# isa_fdc.net
KiCad netlist of a schematic drawn in Altium Designer
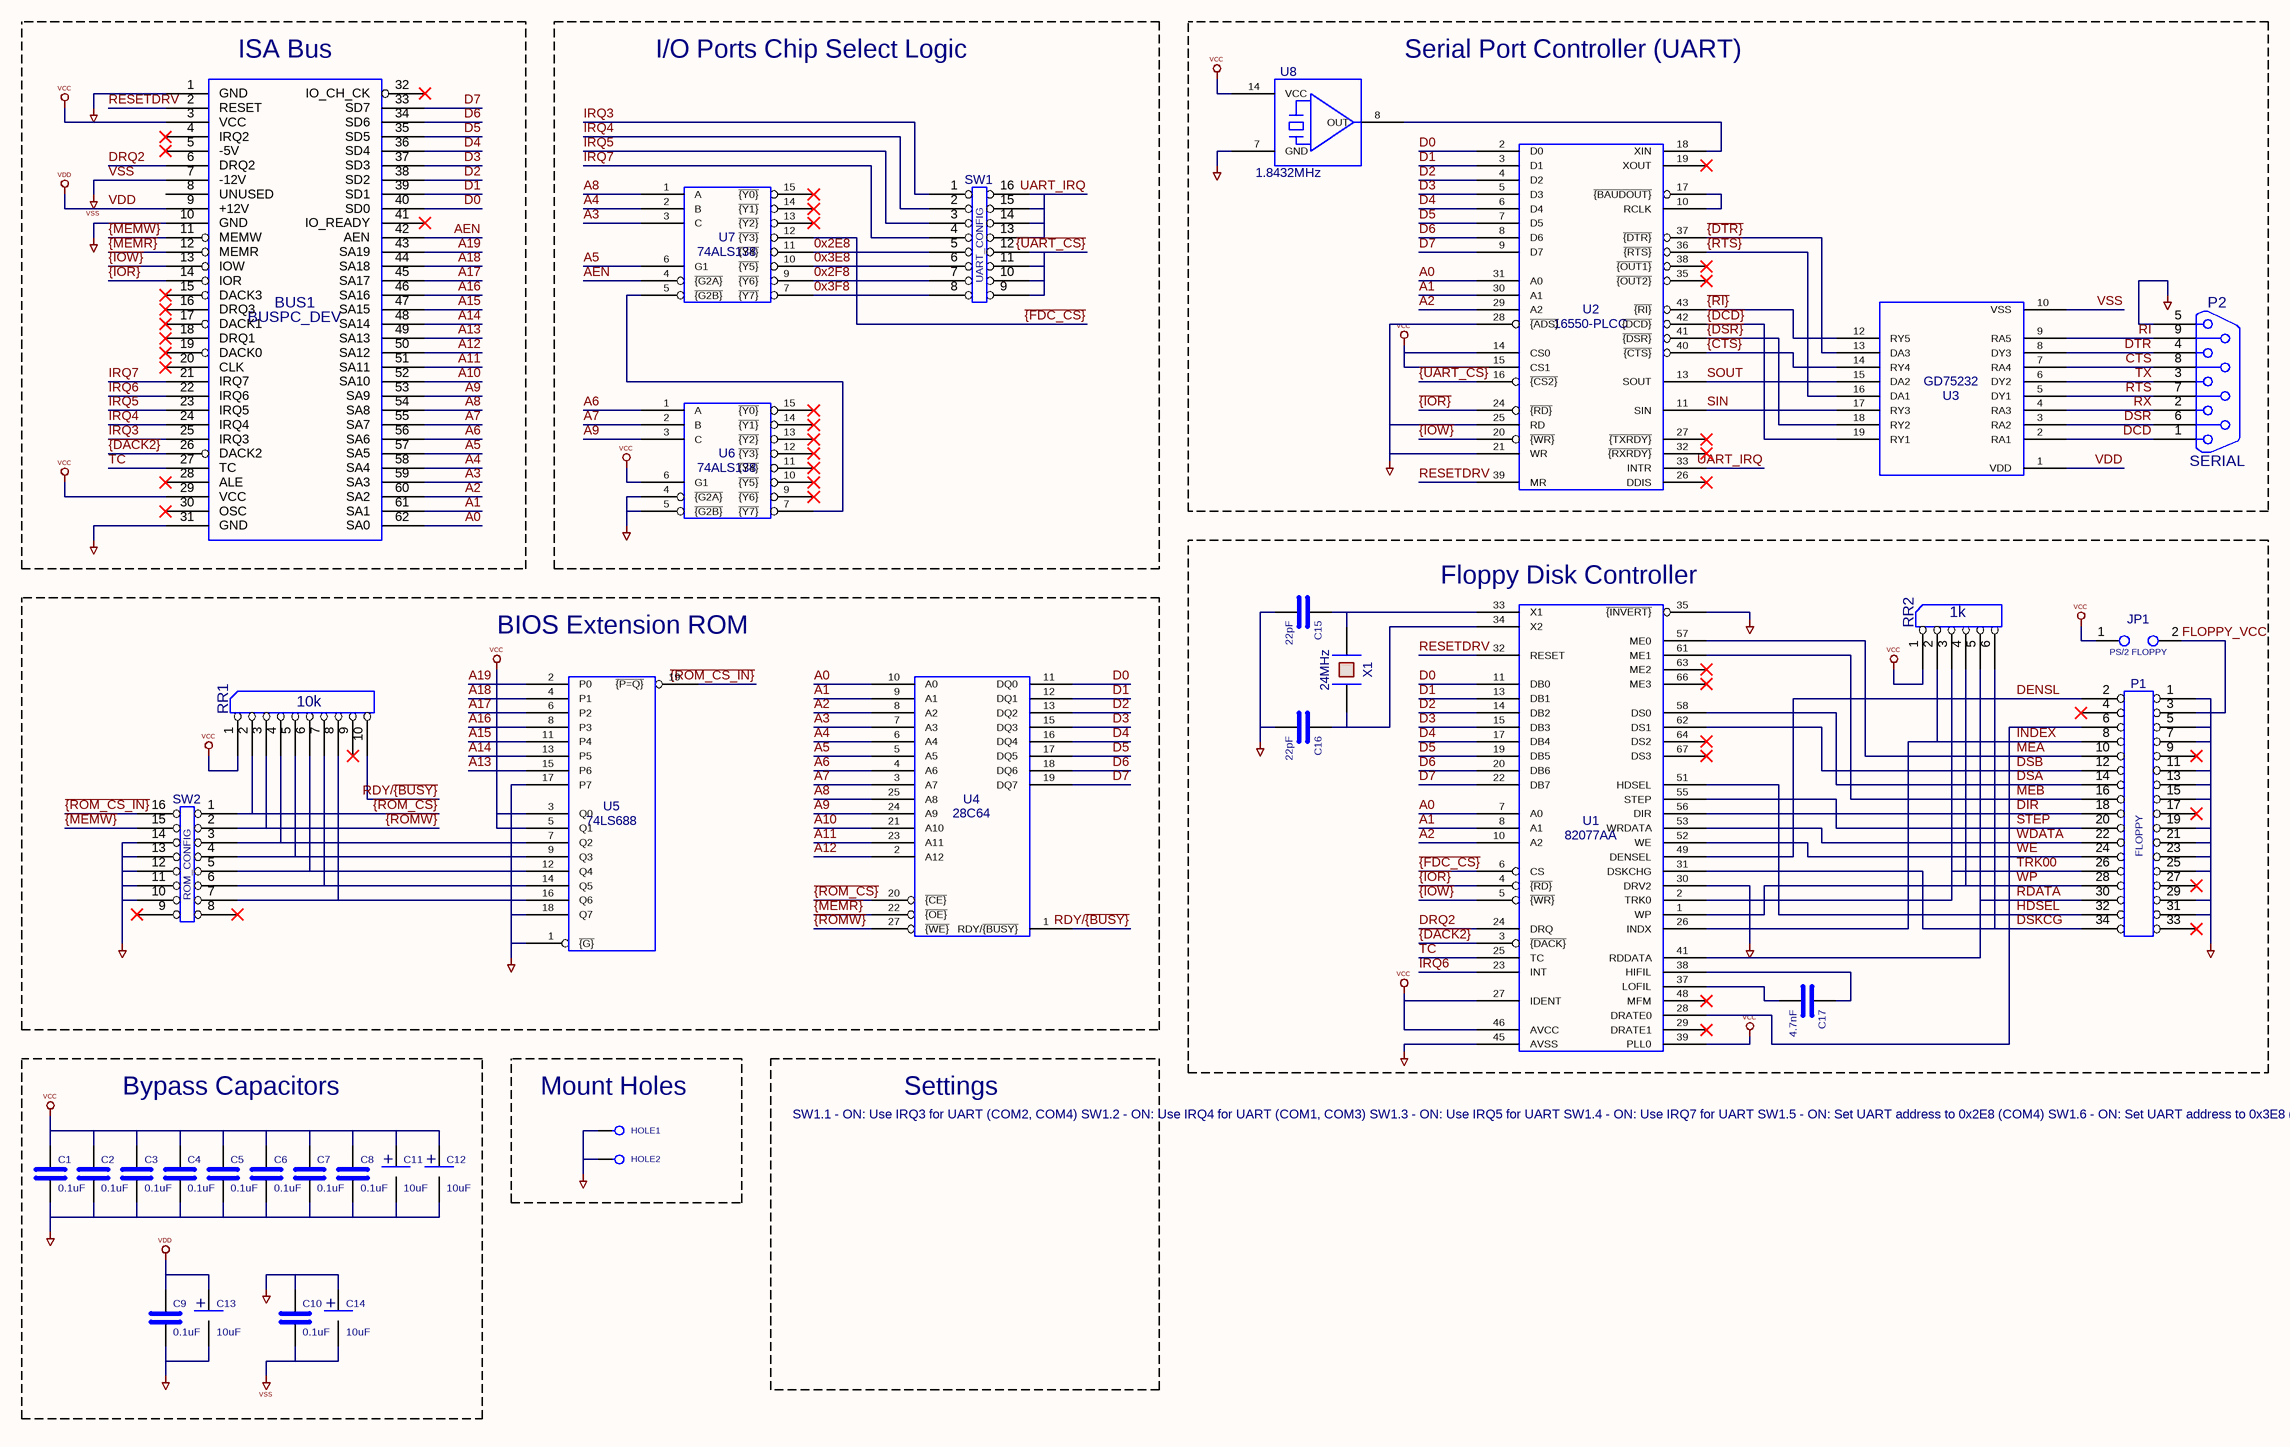
[diagram p0: isa_fdc.SchDoc]

(export (version "E")
  (design (tool "Eeschema 10.0.6"))
  (components
    (comp (ref "BUS1") (value "BUSPC_DEV") (libsource (lib "isa_fdc-rescue") (part "BUSPC_DEV")))
    (comp (ref "C1") (value "0.1uF") (libsource (lib "isa_fdc-rescue") (part "C")))
    (comp (ref "C2") (value "0.1uF") (libsource (lib "isa_fdc-rescue") (part "C")))
    (comp (ref "C3") (value "0.1uF") (libsource (lib "isa_fdc-rescue") (part "C")))
    (comp (ref "C4") (value "0.1uF") (libsource (lib "isa_fdc-rescue") (part "C")))
    (comp (ref "C5") (value "0.1uF") (libsource (lib "isa_fdc-rescue") (part "C")))
    (comp (ref "C6") (value "0.1uF") (libsource (lib "isa_fdc-rescue") (part "C")))
    (comp (ref "C7") (value "0.1uF") (libsource (lib "isa_fdc-rescue") (part "C")))
    (comp (ref "C8") (value "0.1uF") (libsource (lib "isa_fdc-rescue") (part "C")))
    (comp (ref "C9") (value "0.1uF") (libsource (lib "isa_fdc-rescue") (part "C")))
    (comp (ref "C10") (value "0.1uF") (libsource (lib "isa_fdc-rescue") (part "C")))
    (comp (ref "C11") (value "10uF") (libsource (lib "isa_fdc-rescue") (part "CP1")))
    (comp (ref "C12") (value "10uF") (libsource (lib "isa_fdc-rescue") (part "CP1")))
    (comp (ref "C13") (value "10uF") (libsource (lib "isa_fdc-rescue") (part "CP1")))
    (comp (ref "C14") (value "10uF") (libsource (lib "isa_fdc-rescue") (part "CP1")))
    (comp (ref "C15") (value "22pF") (libsource (lib "isa_fdc-rescue") (part "C")))
    (comp (ref "C16") (value "22pF") (libsource (lib "isa_fdc-rescue") (part "C")))
    (comp (ref "C17") (value "4.7nF") (libsource (lib "isa_fdc-rescue") (part "C")))
    (comp (ref "HOLE1") (value "CONN_1") (libsource (lib "isa_fdc-rescue") (part "CONN_1")))
    (comp (ref "HOLE2") (value "CONN_1") (libsource (lib "isa_fdc-rescue") (part "CONN_1")))
    (comp (ref "JP1") (value "PS/2 FLOPPY") (libsource (lib "isa_fdc-rescue") (part "JUMPER")))
    (comp (ref "P1") (value "FLOPPY") (libsource (lib "isa_fdc-rescue") (part "CONN_17X2")))
    (comp (ref "P2") (value "SERIAL") (libsource (lib "isa_fdc-rescue") (part "DB9")))
    (comp (ref "RR1") (value "10k") (libsource (lib "isa_fdc-rescue") (part "RR9")))
    (comp (ref "RR2") (value "1k") (libsource (lib "isa_fdc-rescue") (part "RR5")))
    (comp (ref "SW1") (value "UART_CONFIG") (libsource (lib "") (part "DIL16_1")))
    (comp (ref "SW2") (value "ROM_CONFIG") (libsource (lib "isa_fdc-rescue") (part "DIL16")))
    (comp (ref "U1") (value "82077AA") (libsource (lib "isa_fdc-rescue") (part "82077AA")))
    (comp (ref "U2") (value "16550-PLCC") (libsource (lib "isa_fdc-rescue") (part "16550-PLCC")))
    (comp (ref "U3") (value "GD75232") (libsource (lib "isa_fdc-rescue") (part "GD75232")))
    (comp (ref "U4") (value "28C64") (libsource (lib "isa_fdc-rescue") (part "28C64")))
    (comp (ref "U5") (value "74LS688") (libsource (lib "isa_fdc-rescue") (part "74LS688")))
    (comp (ref "U6") (value "74ALS138") (libsource (lib "isa_fdc-rescue") (part "74LS138")))
    (comp (ref "U7") (value "74ALS138") (libsource (lib "isa_fdc-rescue") (part "74LS138")))
    (comp (ref "U8") (value "1.8432MHz") (libsource (lib "isa_fdc-rescue") (part "OSC")))
    (comp (ref "X1") (value "24MHz") (libsource (lib "isa_fdc-rescue") (part "CRYSTAL")))
  )
  (nets
    (net (code "1") (name "/0x2E8") (class "Default")
      (node (ref "SW1") (pin "5") (pinfunction "5_5") (pintype "passive"))
      (node (ref "U7") (pin "11") (pinfunction "~{{Y4}}_11") (pintype "passive"))
    )
    (net (code "2") (name "/0x2F8") (class "Default")
      (node (ref "SW1") (pin "7") (pinfunction "7_7") (pintype "passive"))
      (node (ref "U7") (pin "9") (pinfunction "~{{Y6}}_9") (pintype "passive"))
    )
    (net (code "3") (name "/0x3E8") (class "Default")
      (node (ref "SW1") (pin "6") (pinfunction "6_6") (pintype "passive"))
      (node (ref "U7") (pin "10") (pinfunction "~{{Y5}}_10") (pintype "passive"))
    )
    (net (code "4") (name "/0x3F8") (class "Default")
      (node (ref "SW1") (pin "8") (pinfunction "8_8") (pintype "passive"))
      (node (ref "U7") (pin "7") (pinfunction "~{{Y7}}_7") (pintype "passive"))
    )
    (net (code "5") (name "/A0") (class "Default")
      (node (ref "BUS1") (pin "62") (pinfunction "SA0_62") (pintype "passive"))
      (node (ref "U1") (pin "7") (pinfunction "A0_7") (pintype "passive"))
      (node (ref "U2") (pin "31") (pinfunction "A0_31") (pintype "passive"))
      (node (ref "U4") (pin "10") (pinfunction "A0_10") (pintype "passive"))
    )
    (net (code "6") (name "/A1") (class "Default")
      (node (ref "BUS1") (pin "61") (pinfunction "SA1_61") (pintype "passive"))
      (node (ref "U1") (pin "8") (pinfunction "A1_8") (pintype "passive"))
      (node (ref "U2") (pin "30") (pinfunction "A1_30") (pintype "passive"))
      (node (ref "U4") (pin "9") (pinfunction "A1_9") (pintype "passive"))
    )
    (net (code "7") (name "/A2") (class "Default")
      (node (ref "BUS1") (pin "60") (pinfunction "SA2_60") (pintype "passive"))
      (node (ref "U1") (pin "10") (pinfunction "A2_10") (pintype "passive"))
      (node (ref "U2") (pin "29") (pinfunction "A2_29") (pintype "passive"))
      (node (ref "U4") (pin "8") (pinfunction "A2_8") (pintype "passive"))
    )
    (net (code "8") (name "/A3") (class "Default")
      (node (ref "BUS1") (pin "59") (pinfunction "SA3_59") (pintype "passive"))
      (node (ref "U4") (pin "7") (pinfunction "A3_7") (pintype "passive"))
      (node (ref "U7") (pin "3") (pinfunction "C_3") (pintype "passive"))
    )
    (net (code "9") (name "/A4") (class "Default")
      (node (ref "BUS1") (pin "58") (pinfunction "SA4_58") (pintype "passive"))
      (node (ref "U4") (pin "6") (pinfunction "A4_6") (pintype "passive"))
      (node (ref "U7") (pin "2") (pinfunction "B_2") (pintype "passive"))
    )
    (net (code "10") (name "/A5") (class "Default")
      (node (ref "BUS1") (pin "57") (pinfunction "SA5_57") (pintype "passive"))
      (node (ref "U4") (pin "5") (pinfunction "A5_5") (pintype "passive"))
      (node (ref "U7") (pin "6") (pinfunction "G1_6") (pintype "passive"))
    )
    (net (code "11") (name "/A6") (class "Default")
      (node (ref "BUS1") (pin "56") (pinfunction "SA6_56") (pintype "passive"))
      (node (ref "U4") (pin "4") (pinfunction "A6_4") (pintype "passive"))
      (node (ref "U6") (pin "1") (pinfunction "A_1") (pintype "passive"))
    )
    (net (code "12") (name "/A7") (class "Default")
      (node (ref "BUS1") (pin "55") (pinfunction "SA7_55") (pintype "passive"))
      (node (ref "U4") (pin "3") (pinfunction "A7_3") (pintype "passive"))
      (node (ref "U6") (pin "2") (pinfunction "B_2") (pintype "passive"))
    )
    (net (code "13") (name "/A8") (class "Default")
      (node (ref "BUS1") (pin "54") (pinfunction "SA8_54") (pintype "passive"))
      (node (ref "U4") (pin "25") (pinfunction "A8_25") (pintype "passive"))
      (node (ref "U7") (pin "1") (pinfunction "A_1") (pintype "passive"))
    )
    (net (code "14") (name "/A9") (class "Default")
      (node (ref "BUS1") (pin "53") (pinfunction "SA9_53") (pintype "passive"))
      (node (ref "U4") (pin "24") (pinfunction "A9_24") (pintype "passive"))
      (node (ref "U6") (pin "3") (pinfunction "C_3") (pintype "passive"))
    )
    (net (code "15") (name "/A10") (class "Default")
      (node (ref "BUS1") (pin "52") (pinfunction "SA10_52") (pintype "passive"))
      (node (ref "U4") (pin "21") (pinfunction "A10_21") (pintype "passive"))
    )
    (net (code "16") (name "/A11") (class "Default")
      (node (ref "BUS1") (pin "51") (pinfunction "SA11_51") (pintype "passive"))
      (node (ref "U4") (pin "23") (pinfunction "A11_23") (pintype "passive"))
    )
    (net (code "17") (name "/A12") (class "Default")
      (node (ref "BUS1") (pin "50") (pinfunction "SA12_50") (pintype "passive"))
      (node (ref "U4") (pin "2") (pinfunction "A12_2") (pintype "passive"))
    )
    (net (code "18") (name "/A13") (class "Default")
      (node (ref "BUS1") (pin "49") (pinfunction "SA13_49") (pintype "passive"))
      (node (ref "U5") (pin "15") (pinfunction "P6_15") (pintype "passive"))
    )
    (net (code "19") (name "/A14") (class "Default")
      (node (ref "BUS1") (pin "48") (pinfunction "SA14_48") (pintype "passive"))
      (node (ref "U5") (pin "13") (pinfunction "P5_13") (pintype "passive"))
    )
    (net (code "20") (name "/A15") (class "Default")
      (node (ref "BUS1") (pin "47") (pinfunction "SA15_47") (pintype "passive"))
      (node (ref "U5") (pin "11") (pinfunction "P4_11") (pintype "passive"))
    )
    (net (code "21") (name "/A16") (class "Default")
      (node (ref "BUS1") (pin "46") (pinfunction "SA16_46") (pintype "passive"))
      (node (ref "U5") (pin "8") (pinfunction "P3_8") (pintype "passive"))
    )
    (net (code "22") (name "/A17") (class "Default")
      (node (ref "BUS1") (pin "45") (pinfunction "SA17_45") (pintype "passive"))
      (node (ref "U5") (pin "6") (pinfunction "P2_6") (pintype "passive"))
    )
    (net (code "23") (name "/A18") (class "Default")
      (node (ref "BUS1") (pin "44") (pinfunction "SA18_44") (pintype "passive"))
      (node (ref "U5") (pin "4") (pinfunction "P1_4") (pintype "passive"))
    )
    (net (code "24") (name "/A19") (class "Default")
      (node (ref "BUS1") (pin "43") (pinfunction "SA19_43") (pintype "passive"))
      (node (ref "U5") (pin "2") (pinfunction "P0_2") (pintype "passive"))
    )
    (net (code "25") (name "/AEN") (class "Default")
      (node (ref "BUS1") (pin "42") (pinfunction "AEN_42") (pintype "passive"))
      (node (ref "U7") (pin "4") (pinfunction "~{{G2A}}_4") (pintype "passive"))
    )
    (net (code "26") (name "/CTS") (class "Default")
      (node (ref "P2") (pin "8") (pinfunction "P8_8") (pintype "passive"))
      (node (ref "U3") (pin "7") (pinfunction "RA4_7") (pintype "passive"))
    )
    (net (code "27") (name "/D0") (class "Default")
      (node (ref "BUS1") (pin "40") (pinfunction "SD0_40") (pintype "passive"))
      (node (ref "U1") (pin "11") (pinfunction "DB0_11") (pintype "passive"))
      (node (ref "U2") (pin "2") (pinfunction "D0_2") (pintype "passive"))
      (node (ref "U4") (pin "11") (pinfunction "DQ0_11") (pintype "passive"))
    )
    (net (code "28") (name "/D1") (class "Default")
      (node (ref "BUS1") (pin "39") (pinfunction "SD1_39") (pintype "passive"))
      (node (ref "U1") (pin "13") (pinfunction "DB1_13") (pintype "passive"))
      (node (ref "U2") (pin "3") (pinfunction "D1_3") (pintype "passive"))
      (node (ref "U4") (pin "12") (pinfunction "DQ1_12") (pintype "passive"))
    )
    (net (code "29") (name "/D2") (class "Default")
      (node (ref "BUS1") (pin "38") (pinfunction "SD2_38") (pintype "passive"))
      (node (ref "U1") (pin "14") (pinfunction "DB2_14") (pintype "passive"))
      (node (ref "U2") (pin "4") (pinfunction "D2_4") (pintype "passive"))
      (node (ref "U4") (pin "13") (pinfunction "DQ2_13") (pintype "passive"))
    )
    (net (code "30") (name "/D3") (class "Default")
      (node (ref "BUS1") (pin "37") (pinfunction "SD3_37") (pintype "passive"))
      (node (ref "U1") (pin "15") (pinfunction "DB3_15") (pintype "passive"))
      (node (ref "U2") (pin "5") (pinfunction "D3_5") (pintype "passive"))
      (node (ref "U4") (pin "15") (pinfunction "DQ3_15") (pintype "passive"))
    )
    (net (code "31") (name "/D4") (class "Default")
      (node (ref "BUS1") (pin "36") (pinfunction "SD4_36") (pintype "passive"))
      (node (ref "U1") (pin "17") (pinfunction "DB4_17") (pintype "passive"))
      (node (ref "U2") (pin "6") (pinfunction "D4_6") (pintype "passive"))
      (node (ref "U4") (pin "16") (pinfunction "DQ4_16") (pintype "passive"))
    )
    (net (code "32") (name "/D5") (class "Default")
      (node (ref "BUS1") (pin "35") (pinfunction "SD5_35") (pintype "passive"))
      (node (ref "U1") (pin "19") (pinfunction "DB5_19") (pintype "passive"))
      (node (ref "U2") (pin "7") (pinfunction "D5_7") (pintype "passive"))
      (node (ref "U4") (pin "17") (pinfunction "DQ5_17") (pintype "passive"))
    )
    (net (code "33") (name "/D6") (class "Default")
      (node (ref "BUS1") (pin "34") (pinfunction "SD6_34") (pintype "passive"))
      (node (ref "U1") (pin "20") (pinfunction "DB6_20") (pintype "passive"))
      (node (ref "U2") (pin "8") (pinfunction "D6_8") (pintype "passive"))
      (node (ref "U4") (pin "18") (pinfunction "DQ6_18") (pintype "passive"))
    )
    (net (code "34") (name "/D7") (class "Default")
      (node (ref "BUS1") (pin "33") (pinfunction "SD7_33") (pintype "passive"))
      (node (ref "U1") (pin "22") (pinfunction "DB7_22") (pintype "passive"))
      (node (ref "U2") (pin "9") (pinfunction "D7_9") (pintype "passive"))
      (node (ref "U4") (pin "19") (pinfunction "DQ7_19") (pintype "passive"))
    )
    (net (code "35") (name "/DCD") (class "Default")
      (node (ref "P2") (pin "1") (pinfunction "1_1") (pintype "passive"))
      (node (ref "U3") (pin "2") (pinfunction "RA1_2") (pintype "passive"))
    )
    (net (code "36") (name "/DENSL") (class "Default")
      (node (ref "P1") (pin "2") (pinfunction "P2_2") (pintype "passive"))
      (node (ref "U1") (pin "49") (pinfunction "DENSEL_49") (pintype "passive"))
    )
    (net (code "37") (name "/DIR") (class "Default")
      (node (ref "P1") (pin "18") (pinfunction "P18_18") (pintype "passive"))
      (node (ref "U1") (pin "56") (pinfunction "DIR_56") (pintype "passive"))
    )
    (net (code "38") (name "/DRQ2") (class "Default")
      (node (ref "BUS1") (pin "6") (pinfunction "DRQ2_6") (pintype "passive"))
      (node (ref "U1") (pin "24") (pinfunction "DRQ_24") (pintype "passive"))
    )
    (net (code "39") (name "/DSA") (class "Default")
      (node (ref "P1") (pin "14") (pinfunction "P14_14") (pintype "passive"))
      (node (ref "U1") (pin "58") (pinfunction "DS0_58") (pintype "passive"))
    )
    (net (code "40") (name "/DSB") (class "Default")
      (node (ref "P1") (pin "12") (pinfunction "P12_12") (pintype "passive"))
      (node (ref "U1") (pin "62") (pinfunction "DS1_62") (pintype "passive"))
    )
    (net (code "41") (name "/DSKCG") (class "Default")
      (node (ref "P1") (pin "34") (pinfunction "P34_34") (pintype "passive"))
      (node (ref "RR2") (pin "6") (pinfunction "6_6") (pintype "passive"))
      (node (ref "U1") (pin "31") (pinfunction "DSKCHG_31") (pintype "passive"))
    )
    (net (code "42") (name "/DSR") (class "Default")
      (node (ref "P2") (pin "6") (pinfunction "P6_6") (pintype "passive"))
      (node (ref "U3") (pin "3") (pinfunction "RA2_3") (pintype "passive"))
    )
    (net (code "43") (name "/DTR") (class "Default")
      (node (ref "P2") (pin "4") (pinfunction "4_4") (pintype "passive"))
      (node (ref "U3") (pin "8") (pinfunction "DY3_8") (pintype "passive"))
    )
    (net (code "44") (name "/FLOPPY_VCC") (class "Default")
      (node (ref "JP1") (pin "2") (pinfunction "2_2") (pintype "passive"))
      (node (ref "P1") (pin "3") (pinfunction "P3_3") (pintype "passive"))
    )
    (net (code "45") (name "/HDSEL") (class "Default")
      (node (ref "P1") (pin "32") (pinfunction "P32_32") (pintype "passive"))
      (node (ref "U1") (pin "51") (pinfunction "HDSEL_51") (pintype "passive"))
    )
    (net (code "46") (name "/INDEX") (class "Default")
      (node (ref "P1") (pin "8") (pinfunction "P8_8") (pintype "passive"))
      (node (ref "RR2") (pin "2") (pinfunction "2_2") (pintype "passive"))
      (node (ref "U1") (pin "26") (pinfunction "INDX_26") (pintype "passive"))
    )
    (net (code "47") (name "/IRQ3") (class "Default")
      (node (ref "BUS1") (pin "25") (pinfunction "IRQ3_25") (pintype "passive"))
      (node (ref "SW1") (pin "1") (pinfunction "1_1") (pintype "passive"))
    )
    (net (code "48") (name "/IRQ4") (class "Default")
      (node (ref "BUS1") (pin "24") (pinfunction "IRQ4_24") (pintype "passive"))
      (node (ref "SW1") (pin "2") (pinfunction "2_2") (pintype "passive"))
    )
    (net (code "49") (name "/IRQ5") (class "Default")
      (node (ref "BUS1") (pin "23") (pinfunction "IRQ5_23") (pintype "passive"))
      (node (ref "SW1") (pin "3") (pinfunction "3_3") (pintype "passive"))
    )
    (net (code "50") (name "/IRQ6") (class "Default")
      (node (ref "BUS1") (pin "22") (pinfunction "IRQ6_22") (pintype "passive"))
      (node (ref "U1") (pin "23") (pinfunction "INT_23") (pintype "passive"))
    )
    (net (code "51") (name "/IRQ7") (class "Default")
      (node (ref "BUS1") (pin "21") (pinfunction "IRQ7_21") (pintype "passive"))
      (node (ref "SW1") (pin "4") (pinfunction "4_4") (pintype "passive"))
    )
    (net (code "52") (name "/MEA") (class "Default")
      (node (ref "P1") (pin "10") (pinfunction "P10_10") (pintype "passive"))
      (node (ref "U1") (pin "57") (pinfunction "ME0_57") (pintype "passive"))
    )
    (net (code "53") (name "/MEB") (class "Default")
      (node (ref "P1") (pin "16") (pinfunction "P16_16") (pintype "passive"))
      (node (ref "U1") (pin "61") (pinfunction "ME1_61") (pintype "passive"))
    )
    (net (code "54") (name "/RDATA") (class "Default")
      (node (ref "P1") (pin "30") (pinfunction "P30_30") (pintype "passive"))
      (node (ref "RR2") (pin "5") (pinfunction "5_5") (pintype "passive"))
      (node (ref "U1") (pin "41") (pinfunction "RDDATA_41") (pintype "passive"))
    )
    (net (code "55") (name "/RDY{slash}~{{BUSY}}") (class "Default")
      (node (ref "RR1") (pin "10") (pinfunction "10_10") (pintype "passive"))
      (node (ref "U4") (pin "1") (pinfunction "RDY/~{{BUSY}}_1") (pintype "passive"))
    )
    (net (code "56") (name "/RESETDRV") (class "Default")
      (node (ref "BUS1") (pin "2") (pinfunction "RESET_2") (pintype "passive"))
      (node (ref "U1") (pin "32") (pinfunction "RESET_32") (pintype "passive"))
      (node (ref "U2") (pin "39") (pinfunction "MR_39") (pintype "passive"))
    )
    (net (code "57") (name "/RI") (class "Default")
      (node (ref "P2") (pin "9") (pinfunction "P9_9") (pintype "passive"))
      (node (ref "U3") (pin "9") (pinfunction "RA5_9") (pintype "passive"))
    )
    (net (code "58") (name "/RTS") (class "Default")
      (node (ref "P2") (pin "7") (pinfunction "P7_7") (pintype "passive"))
      (node (ref "U3") (pin "5") (pinfunction "DY1_5") (pintype "passive"))
    )
    (net (code "59") (name "/RX") (class "Default")
      (node (ref "P2") (pin "2") (pinfunction "2_2") (pintype "passive"))
      (node (ref "U3") (pin "4") (pinfunction "RA3_4") (pintype "passive"))
    )
    (net (code "60") (name "/SIN") (class "Default")
      (node (ref "U2") (pin "11") (pinfunction "SIN_11") (pintype "passive"))
      (node (ref "U3") (pin "17") (pinfunction "RY3_17") (pintype "passive"))
    )
    (net (code "61") (name "/SOUT") (class "Default")
      (node (ref "U2") (pin "13") (pinfunction "SOUT_13") (pintype "passive"))
      (node (ref "U3") (pin "15") (pinfunction "DA2_15") (pintype "passive"))
    )
    (net (code "62") (name "/STEP") (class "Default")
      (node (ref "P1") (pin "20") (pinfunction "P20_20") (pintype "passive"))
      (node (ref "U1") (pin "55") (pinfunction "STEP_55") (pintype "passive"))
    )
    (net (code "63") (name "/TC") (class "Default")
      (node (ref "BUS1") (pin "27") (pinfunction "TC_27") (pintype "passive"))
      (node (ref "U1") (pin "25") (pinfunction "TC_25") (pintype "passive"))
    )
    (net (code "64") (name "/TRK00") (class "Default")
      (node (ref "P1") (pin "26") (pinfunction "P26_26") (pintype "passive"))
      (node (ref "RR2") (pin "3") (pinfunction "3_3") (pintype "passive"))
      (node (ref "U1") (pin "2") (pinfunction "TRK0_2") (pintype "passive"))
    )
    (net (code "65") (name "/TX") (class "Default")
      (node (ref "P2") (pin "3") (pinfunction "3_3") (pintype "passive"))
      (node (ref "U3") (pin "6") (pinfunction "DY2_6") (pintype "passive"))
    )
    (net (code "66") (name "/UART_IRQ") (class "Default")
      (node (ref "SW1") (pin "13") (pinfunction "13_13") (pintype "passive"))
      (node (ref "SW1") (pin "14") (pinfunction "14_14") (pintype "passive"))
      (node (ref "SW1") (pin "15") (pinfunction "15_15") (pintype "passive"))
      (node (ref "SW1") (pin "16") (pinfunction "16_16") (pintype "passive"))
      (node (ref "U2") (pin "33") (pinfunction "INTR_33") (pintype "passive"))
    )
    (net (code "67") (name "/WDATA") (class "Default")
      (node (ref "P1") (pin "22") (pinfunction "P22_22") (pintype "passive"))
      (node (ref "U1") (pin "53") (pinfunction "WRDATA_53") (pintype "passive"))
    )
    (net (code "68") (name "/WE") (class "Default")
      (node (ref "P1") (pin "24") (pinfunction "P24_24") (pintype "passive"))
      (node (ref "U1") (pin "52") (pinfunction "WE_52") (pintype "passive"))
    )
    (net (code "69") (name "/WP") (class "Default")
      (node (ref "P1") (pin "28") (pinfunction "P28_28") (pintype "passive"))
      (node (ref "RR2") (pin "4") (pinfunction "4_4") (pintype "passive"))
      (node (ref "U1") (pin "1") (pinfunction "WP_1") (pintype "passive"))
    )
    (net (code "70") (name "/~{{CTS}}") (class "Default")
      (node (ref "U2") (pin "40") (pinfunction "~{{CTS}}_40") (pintype "passive"))
      (node (ref "U3") (pin "14") (pinfunction "RY4_14") (pintype "passive"))
    )
    (net (code "71") (name "/~{{DACK2}}") (class "Default")
      (node (ref "BUS1") (pin "26") (pinfunction "DACK2_26") (pintype "passive"))
      (node (ref "U1") (pin "3") (pinfunction "~{{DACK}}_3") (pintype "passive"))
    )
    (net (code "72") (name "/~{{DCD}}") (class "Default")
      (node (ref "U2") (pin "42") (pinfunction "~{{DCD}}_42") (pintype "passive"))
      (node (ref "U3") (pin "19") (pinfunction "RY1_19") (pintype "passive"))
    )
    (net (code "73") (name "/~{{DSR}}") (class "Default")
      (node (ref "U2") (pin "41") (pinfunction "~{{DSR}}_41") (pintype "passive"))
      (node (ref "U3") (pin "18") (pinfunction "RY2_18") (pintype "passive"))
    )
    (net (code "74") (name "/~{{DTR}}") (class "Default")
      (node (ref "U2") (pin "37") (pinfunction "~{{DTR}}_37") (pintype "passive"))
      (node (ref "U3") (pin "13") (pinfunction "DA3_13") (pintype "passive"))
    )
    (net (code "75") (name "/~{{FDC_CS}}") (class "Default")
      (node (ref "U1") (pin "6") (pinfunction "CS_6") (pintype "passive"))
      (node (ref "U7") (pin "12") (pinfunction "~{{Y3}}_12") (pintype "passive"))
    )
    (net (code "76") (name "/~{{IOR}}") (class "Default")
      (node (ref "BUS1") (pin "14") (pinfunction "IOR_14") (pintype "passive"))
      (node (ref "U1") (pin "4") (pinfunction "~{{RD}}_4") (pintype "passive"))
      (node (ref "U2") (pin "24") (pinfunction "~{{RD}}_24") (pintype "passive"))
    )
    (net (code "77") (name "/~{{IOW}}") (class "Default")
      (node (ref "BUS1") (pin "13") (pinfunction "IOW_13") (pintype "passive"))
      (node (ref "U1") (pin "5") (pinfunction "~{{WR}}_5") (pintype "passive"))
      (node (ref "U2") (pin "20") (pinfunction "~{{WR}}_20") (pintype "passive"))
    )
    (net (code "78") (name "/~{{MEMR}}") (class "Default")
      (node (ref "BUS1") (pin "12") (pinfunction "MEMR_12") (pintype "passive"))
      (node (ref "U4") (pin "22") (pinfunction "~{{OE}}_22") (pintype "passive"))
    )
    (net (code "79") (name "/~{{MEMW}}") (class "Default")
      (node (ref "BUS1") (pin "11") (pinfunction "MEMW_11") (pintype "passive"))
      (node (ref "SW2") (pin "15") (pinfunction "15_15") (pintype "passive"))
    )
    (net (code "80") (name "/~{{RI}}") (class "Default")
      (node (ref "U2") (pin "43") (pinfunction "~{{RI}}_43") (pintype "passive"))
      (node (ref "U3") (pin "12") (pinfunction "RY5_12") (pintype "passive"))
    )
    (net (code "81") (name "/~{{ROMW}}") (class "Default")
      (node (ref "RR1") (pin "3") (pinfunction "3_3") (pintype "passive"))
      (node (ref "SW2") (pin "2") (pinfunction "2_2") (pintype "passive"))
      (node (ref "U4") (pin "27") (pinfunction "~{{WE}}_27") (pintype "passive"))
    )
    (net (code "82") (name "/~{{ROM_CS_IN}}") (class "Default")
      (node (ref "SW2") (pin "16") (pinfunction "16_16") (pintype "passive"))
      (node (ref "U5") (pin "19") (pinfunction "~{{P=Q}}_19") (pintype "passive"))
    )
    (net (code "83") (name "/~{{ROM_CS}}") (class "Default")
      (node (ref "RR1") (pin "2") (pinfunction "2_2") (pintype "passive"))
      (node (ref "SW2") (pin "1") (pinfunction "1_1") (pintype "passive"))
      (node (ref "U4") (pin "20") (pinfunction "~{{CE}}_20") (pintype "passive"))
    )
    (net (code "84") (name "/~{{RTS}}") (class "Default")
      (node (ref "U2") (pin "36") (pinfunction "~{{RTS}}_36") (pintype "passive"))
      (node (ref "U3") (pin "16") (pinfunction "DA1_16") (pintype "passive"))
    )
    (net (code "85") (name "/~{{UART_CS}}") (class "Default")
      (node (ref "SW1") (pin "10") (pinfunction "10_10") (pintype "passive"))
      (node (ref "SW1") (pin "11") (pinfunction "11_11") (pintype "passive"))
      (node (ref "SW1") (pin "12") (pinfunction "12_12") (pintype "passive"))
      (node (ref "SW1") (pin "9") (pinfunction "9_9") (pintype "passive"))
      (node (ref "U2") (pin "16") (pinfunction "~{{CS2}}_16") (pintype "passive"))
    )
    (net (code "86") (name "GND") (class "Default")
      (node (ref "BUS1") (pin "1") (pinfunction "GND_1") (pintype "passive"))
      (node (ref "BUS1") (pin "10") (pinfunction "GND_10") (pintype "passive"))
      (node (ref "BUS1") (pin "31") (pinfunction "GND_31") (pintype "passive"))
      (node (ref "C1") (pin "2") (pinfunction "2_2") (pintype "passive"))
      (node (ref "C10") (pin "1") (pinfunction "1_1") (pintype "passive"))
      (node (ref "C11") (pin "2") (pinfunction "2_2") (pintype "passive"))
      (node (ref "C12") (pin "2") (pinfunction "2_2") (pintype "passive"))
      (node (ref "C13") (pin "2") (pinfunction "2_2") (pintype "passive"))
      (node (ref "C14") (pin "1") (pinfunction "1_1") (pintype "passive"))
      (node (ref "C15") (pin "2") (pinfunction "2_2") (pintype "passive"))
      (node (ref "C16") (pin "2") (pinfunction "2_2") (pintype "passive"))
      (node (ref "C2") (pin "2") (pinfunction "2_2") (pintype "passive"))
      (node (ref "C3") (pin "2") (pinfunction "2_2") (pintype "passive"))
      (node (ref "C4") (pin "2") (pinfunction "2_2") (pintype "passive"))
      (node (ref "C5") (pin "2") (pinfunction "2_2") (pintype "passive"))
      (node (ref "C6") (pin "2") (pinfunction "2_2") (pintype "passive"))
      (node (ref "C7") (pin "2") (pinfunction "2_2") (pintype "passive"))
      (node (ref "C8") (pin "2") (pinfunction "2_2") (pintype "passive"))
      (node (ref "C9") (pin "2") (pinfunction "2_2") (pintype "passive"))
      (node (ref "HOLE1") (pin "1") (pinfunction "1_1") (pintype "passive"))
      (node (ref "HOLE2") (pin "1") (pinfunction "1_1") (pintype "passive"))
      (node (ref "P1") (pin "1") (pinfunction "P1_1") (pintype "passive"))
      (node (ref "P1") (pin "11") (pinfunction "P11_11") (pintype "passive"))
      (node (ref "P1") (pin "13") (pinfunction "P13_13") (pintype "passive"))
      (node (ref "P1") (pin "15") (pinfunction "P15_15") (pintype "passive"))
      (node (ref "P1") (pin "19") (pinfunction "P19_19") (pintype "passive"))
      (node (ref "P1") (pin "21") (pinfunction "P21_21") (pintype "passive"))
      (node (ref "P1") (pin "23") (pinfunction "P23_23") (pintype "passive"))
      (node (ref "P1") (pin "25") (pinfunction "25_25") (pintype "passive"))
      (node (ref "P1") (pin "29") (pinfunction "P29_29") (pintype "passive"))
      (node (ref "P1") (pin "31") (pinfunction "P31_31") (pintype "passive"))
      (node (ref "P1") (pin "5") (pinfunction "P5_5") (pintype "passive"))
      (node (ref "P1") (pin "7") (pinfunction "P7_7") (pintype "passive"))
      (node (ref "P2") (pin "5") (pinfunction "5_5") (pintype "passive"))
      (node (ref "SW2") (pin "10") (pinfunction "10_10") (pintype "passive"))
      (node (ref "SW2") (pin "11") (pinfunction "11_11") (pintype "passive"))
      (node (ref "SW2") (pin "12") (pinfunction "12_12") (pintype "passive"))
      (node (ref "SW2") (pin "13") (pinfunction "13_13") (pintype "passive"))
      (node (ref "SW2") (pin "14") (pinfunction "14_14") (pintype "passive"))
      (node (ref "U1") (pin "30") (pinfunction "DRV2_30") (pintype "passive"))
      (node (ref "U1") (pin "35") (pinfunction "~{{INVERT}}_35") (pintype "passive"))
      (node (ref "U1") (pin "45") (pinfunction "AVSS_45") (pintype "passive"))
      (node (ref "U2") (pin "21") (pinfunction "WR_21") (pintype "passive"))
      (node (ref "U2") (pin "25") (pinfunction "RD_25") (pintype "passive"))
      (node (ref "U2") (pin "28") (pinfunction "~{{ADS}}_28") (pintype "passive"))
      (node (ref "U5") (pin "1") (pinfunction "~{{G}}_1") (pintype "passive"))
      (node (ref "U5") (pin "17") (pinfunction "P7_17") (pintype "passive"))
      (node (ref "U5") (pin "18") (pinfunction "Q7_18") (pintype "passive"))
      (node (ref "U6") (pin "4") (pinfunction "~{{G2A}}_4") (pintype "passive"))
      (node (ref "U6") (pin "5") (pinfunction "~{{G2B}}_5") (pintype "passive"))
      (node (ref "U8") (pin "7") (pinfunction "GND_7") (pintype "passive"))
    )
    (net (code "87") (name "Net-(P1-P6)") (class "Default")
      (node (ref "P1") (pin "6") (pinfunction "P6_6") (pintype "passive"))
      (node (ref "U1") (pin "28") (pinfunction "DRATE0_28") (pintype "passive"))
    )
    (net (code "88") (name "Net-(U1-HIFIL)") (class "Default")
      (node (ref "C17") (pin "1") (pinfunction "1_1") (pintype "passive"))
      (node (ref "U1") (pin "38") (pinfunction "HIFIL_38") (pintype "passive"))
    )
    (net (code "89") (name "Net-(U1-LOFIL)") (class "Default")
      (node (ref "C17") (pin "2") (pinfunction "2_2") (pintype "passive"))
      (node (ref "U1") (pin "37") (pinfunction "LOFIL_37") (pintype "passive"))
    )
    (net (code "90") (name "Net-(U1-X1)") (class "Default")
      (node (ref "C15") (pin "1") (pinfunction "1_1") (pintype "passive"))
      (node (ref "U1") (pin "33") (pinfunction "X1_33") (pintype "passive"))
      (node (ref "X1") (pin "1") (pinfunction "1_1") (pintype "passive"))
    )
    (net (code "91") (name "Net-(U1-X2)") (class "Default")
      (node (ref "C16") (pin "1") (pinfunction "1_1") (pintype "passive"))
      (node (ref "U1") (pin "34") (pinfunction "X2_34") (pintype "passive"))
      (node (ref "X1") (pin "2") (pinfunction "2_2") (pintype "passive"))
    )
    (net (code "92") (name "Net-(U2-RCLK)") (class "Default")
      (node (ref "U2") (pin "10") (pinfunction "RCLK_10") (pintype "passive"))
      (node (ref "U2") (pin "17") (pinfunction "~{{BAUDOUT}}_17") (pintype "passive"))
    )
    (net (code "93") (name "Net-(U2-XIN)") (class "Default")
      (node (ref "U2") (pin "18") (pinfunction "XIN_18") (pintype "passive"))
      (node (ref "U8") (pin "8") (pinfunction "OUT_8") (pintype "passive"))
    )
    (net (code "94") (name "Net-(U5-Q2)") (class "Default")
      (node (ref "RR1") (pin "4") (pinfunction "4_4") (pintype "passive"))
      (node (ref "SW2") (pin "3") (pinfunction "3_3") (pintype "passive"))
      (node (ref "U5") (pin "7") (pinfunction "Q2_7") (pintype "passive"))
    )
    (net (code "95") (name "Net-(U5-Q3)") (class "Default")
      (node (ref "RR1") (pin "5") (pinfunction "5_5") (pintype "passive"))
      (node (ref "SW2") (pin "4") (pinfunction "4_4") (pintype "passive"))
      (node (ref "U5") (pin "9") (pinfunction "Q3_9") (pintype "passive"))
    )
    (net (code "96") (name "Net-(U5-Q4)") (class "Default")
      (node (ref "RR1") (pin "6") (pinfunction "6_6") (pintype "passive"))
      (node (ref "SW2") (pin "5") (pinfunction "5_5") (pintype "passive"))
      (node (ref "U5") (pin "12") (pinfunction "Q4_12") (pintype "passive"))
    )
    (net (code "97") (name "Net-(U5-Q5)") (class "Default")
      (node (ref "RR1") (pin "7") (pinfunction "7_7") (pintype "passive"))
      (node (ref "SW2") (pin "6") (pinfunction "6_6") (pintype "passive"))
      (node (ref "U5") (pin "14") (pinfunction "Q5_14") (pintype "passive"))
    )
    (net (code "98") (name "Net-(U5-Q6)") (class "Default")
      (node (ref "RR1") (pin "8") (pinfunction "8_8") (pintype "passive"))
      (node (ref "SW2") (pin "7") (pinfunction "7_7") (pintype "passive"))
      (node (ref "U5") (pin "16") (pinfunction "Q6_16") (pintype "passive"))
    )
    (net (code "99") (name "Net-(U6-~{{Y7}})") (class "Default")
      (node (ref "U6") (pin "7") (pinfunction "~{{Y7}}_7") (pintype "passive"))
      (node (ref "U7") (pin "5") (pinfunction "~{{G2B}}_5") (pintype "passive"))
    )
    (net (code "100") (name "VCC") (class "Default")
      (node (ref "BUS1") (pin "29") (pinfunction "VCC_29") (pintype "passive"))
      (node (ref "BUS1") (pin "3") (pinfunction "VCC_3") (pintype "passive"))
      (node (ref "C1") (pin "1") (pinfunction "1_1") (pintype "passive"))
      (node (ref "C11") (pin "1") (pinfunction "1_1") (pintype "passive"))
      (node (ref "C12") (pin "1") (pinfunction "1_1") (pintype "passive"))
      (node (ref "C2") (pin "1") (pinfunction "1_1") (pintype "passive"))
      (node (ref "C3") (pin "1") (pinfunction "1_1") (pintype "passive"))
      (node (ref "C4") (pin "1") (pinfunction "1_1") (pintype "passive"))
      (node (ref "C5") (pin "1") (pinfunction "1_1") (pintype "passive"))
      (node (ref "C6") (pin "1") (pinfunction "1_1") (pintype "passive"))
      (node (ref "C7") (pin "1") (pinfunction "1_1") (pintype "passive"))
      (node (ref "C8") (pin "1") (pinfunction "1_1") (pintype "passive"))
      (node (ref "JP1") (pin "1") (pinfunction "1_1") (pintype "passive"))
      (node (ref "RR1") (pin "1") (pinfunction "COM_1") (pintype "passive"))
      (node (ref "RR2") (pin "1") (pinfunction "COM_1") (pintype "passive"))
      (node (ref "U1") (pin "27") (pinfunction "IDENT_27") (pintype "passive"))
      (node (ref "U1") (pin "39") (pinfunction "PLL0_39") (pintype "passive"))
      (node (ref "U1") (pin "46") (pinfunction "AVCC_46") (pintype "passive"))
      (node (ref "U2") (pin "14") (pinfunction "CS0_14") (pintype "passive"))
      (node (ref "U2") (pin "15") (pinfunction "CS1_15") (pintype "passive"))
      (node (ref "U5") (pin "3") (pinfunction "Q0_3") (pintype "passive"))
      (node (ref "U5") (pin "5") (pinfunction "Q1_5") (pintype "passive"))
      (node (ref "U6") (pin "6") (pinfunction "G1_6") (pintype "passive"))
      (node (ref "U8") (pin "14") (pinfunction "VCC_14") (pintype "passive"))
    )
    (net (code "101") (name "VDD") (class "Default")
      (node (ref "BUS1") (pin "9") (pinfunction "+12V_9") (pintype "passive"))
      (node (ref "C13") (pin "1") (pinfunction "1_1") (pintype "passive"))
      (node (ref "C9") (pin "1") (pinfunction "1_1") (pintype "passive"))
      (node (ref "U3") (pin "1") (pinfunction "VDD_1") (pintype "passive"))
    )
    (net (code "102") (name "VSS") (class "Default")
      (node (ref "BUS1") (pin "7") (pinfunction "-12V_7") (pintype "passive"))
      (node (ref "C10") (pin "2") (pinfunction "2_2") (pintype "passive"))
      (node (ref "C14") (pin "2") (pinfunction "2_2") (pintype "passive"))
      (node (ref "U3") (pin "10") (pinfunction "VSS_10") (pintype "passive"))
    )
    (net (code "103") (name "unconnected-(BUS1--5V-Pad5)") (class "Default")
      (node (ref "BUS1") (pin "5") (pinfunction "-5V_5") (pintype "passive+no_connect"))
    )
    (net (code "104") (name "unconnected-(BUS1-ALE-Pad28)") (class "Default")
      (node (ref "BUS1") (pin "28") (pinfunction "ALE_28") (pintype "passive+no_connect"))
    )
    (net (code "105") (name "unconnected-(BUS1-CLK-Pad20)") (class "Default")
      (node (ref "BUS1") (pin "20") (pinfunction "CLK_20") (pintype "passive+no_connect"))
    )
    (net (code "106") (name "unconnected-(BUS1-DACK0-Pad19)") (class "Default")
      (node (ref "BUS1") (pin "19") (pinfunction "DACK0_19") (pintype "passive+no_connect"))
    )
    (net (code "107") (name "unconnected-(BUS1-DACK1-Pad17)") (class "Default")
      (node (ref "BUS1") (pin "17") (pinfunction "DACK1_17") (pintype "passive+no_connect"))
    )
    (net (code "108") (name "unconnected-(BUS1-DACK3-Pad15)") (class "Default")
      (node (ref "BUS1") (pin "15") (pinfunction "DACK3_15") (pintype "passive+no_connect"))
    )
    (net (code "109") (name "unconnected-(BUS1-DRQ1-Pad18)") (class "Default")
      (node (ref "BUS1") (pin "18") (pinfunction "DRQ1_18") (pintype "passive+no_connect"))
    )
    (net (code "110") (name "unconnected-(BUS1-DRQ3-Pad16)") (class "Default")
      (node (ref "BUS1") (pin "16") (pinfunction "DRQ3_16") (pintype "passive+no_connect"))
    )
    (net (code "111") (name "unconnected-(BUS1-IO_CH_CK-Pad32)") (class "Default")
      (node (ref "BUS1") (pin "32") (pinfunction "IO_CH_CK_32") (pintype "passive+no_connect"))
    )
    (net (code "112") (name "unconnected-(BUS1-IO_READY-Pad41)") (class "Default")
      (node (ref "BUS1") (pin "41") (pinfunction "IO_READY_41") (pintype "passive+no_connect"))
    )
    (net (code "113") (name "unconnected-(BUS1-IRQ2-Pad4)") (class "Default")
      (node (ref "BUS1") (pin "4") (pinfunction "IRQ2_4") (pintype "passive+no_connect"))
    )
    (net (code "114") (name "unconnected-(BUS1-OSC-Pad30)") (class "Default")
      (node (ref "BUS1") (pin "30") (pinfunction "OSC_30") (pintype "passive+no_connect"))
    )
    (net (code "115") (name "unconnected-(BUS1-UNUSED-Pad8)") (class "Default")
      (node (ref "BUS1") (pin "8") (pinfunction "UNUSED_8") (pintype "passive"))
    )
    (net (code "116") (name "unconnected-(P1-P4-Pad4)") (class "Default")
      (node (ref "P1") (pin "4") (pinfunction "P4_4") (pintype "passive+no_connect"))
    )
    (net (code "117") (name "unconnected-(P1-P9-Pad9)") (class "Default")
      (node (ref "P1") (pin "9") (pinfunction "P9_9") (pintype "passive+no_connect"))
    )
    (net (code "118") (name "unconnected-(P1-P17-Pad17)") (class "Default")
      (node (ref "P1") (pin "17") (pinfunction "P17_17") (pintype "passive+no_connect"))
    )
    (net (code "119") (name "unconnected-(P1-P27-Pad27)") (class "Default")
      (node (ref "P1") (pin "27") (pinfunction "P27_27") (pintype "passive+no_connect"))
    )
    (net (code "120") (name "unconnected-(P1-P33-Pad33)") (class "Default")
      (node (ref "P1") (pin "33") (pinfunction "P33_33") (pintype "passive+no_connect"))
    )
    (net (code "121") (name "unconnected-(RR1-Pad9)") (class "Default")
      (node (ref "RR1") (pin "9") (pinfunction "9_9") (pintype "passive+no_connect"))
    )
    (net (code "122") (name "unconnected-(SW2-Pad8)") (class "Default")
      (node (ref "SW2") (pin "8") (pinfunction "8_8") (pintype "passive+no_connect"))
    )
    (net (code "123") (name "unconnected-(SW2-Pad9)") (class "Default")
      (node (ref "SW2") (pin "9") (pinfunction "9_9") (pintype "passive+no_connect"))
    )
    (net (code "124") (name "unconnected-(U1-DRATE1-Pad29)") (class "Default")
      (node (ref "U1") (pin "29") (pinfunction "DRATE1_29") (pintype "passive+no_connect"))
    )
    (net (code "125") (name "unconnected-(U1-DS2-Pad64)") (class "Default")
      (node (ref "U1") (pin "64") (pinfunction "DS2_64") (pintype "passive+no_connect"))
    )
    (net (code "126") (name "unconnected-(U1-DS3-Pad67)") (class "Default")
      (node (ref "U1") (pin "67") (pinfunction "DS3_67") (pintype "passive+no_connect"))
    )
    (net (code "127") (name "unconnected-(U1-GND-Pad9)") (class "Default")
      (node (ref "U1") (pin "9") (pinfunction "GND_9") (pintype "passive"))
    )
    (net (code "128") (name "unconnected-(U1-GND-Pad12)") (class "Default")
      (node (ref "U1") (pin "12") (pinfunction "GND_12") (pintype "passive"))
    )
    (net (code "129") (name "unconnected-(U1-GND-Pad16)") (class "Default")
      (node (ref "U1") (pin "16") (pinfunction "GND_16") (pintype "passive"))
    )
    (net (code "130") (name "unconnected-(U1-GND-Pad21)") (class "Default")
      (node (ref "U1") (pin "21") (pinfunction "GND_21") (pintype "passive"))
    )
    (net (code "131") (name "unconnected-(U1-GND-Pad36)") (class "Default")
      (node (ref "U1") (pin "36") (pinfunction "GND_36") (pintype "passive"))
    )
    (net (code "132") (name "unconnected-(U1-GND-Pad50)") (class "Default")
      (node (ref "U1") (pin "50") (pinfunction "GND_50") (pintype "passive"))
    )
    (net (code "133") (name "unconnected-(U1-GND-Pad54)") (class "Default")
      (node (ref "U1") (pin "54") (pinfunction "GND_54") (pintype "passive"))
    )
    (net (code "134") (name "unconnected-(U1-GND-Pad59)") (class "Default")
      (node (ref "U1") (pin "59") (pinfunction "GND_59") (pintype "passive"))
    )
    (net (code "135") (name "unconnected-(U1-GND-Pad65)") (class "Default")
      (node (ref "U1") (pin "65") (pinfunction "GND_65") (pintype "passive"))
    )
    (net (code "136") (name "unconnected-(U1-ME2-Pad63)") (class "Default")
      (node (ref "U1") (pin "63") (pinfunction "ME2_63") (pintype "passive+no_connect"))
    )
    (net (code "137") (name "unconnected-(U1-ME3-Pad66)") (class "Default")
      (node (ref "U1") (pin "66") (pinfunction "ME3_66") (pintype "passive+no_connect"))
    )
    (net (code "138") (name "unconnected-(U1-MFM-Pad48)") (class "Default")
      (node (ref "U1") (pin "48") (pinfunction "MFM_48") (pintype "passive+no_connect"))
    )
    (net (code "139") (name "unconnected-(U1-NC-Pad42)") (class "Default")
      (node (ref "U1") (pin "42") (pinfunction "NC_42") (pintype "passive"))
    )
    (net (code "140") (name "unconnected-(U1-NC-Pad43)") (class "Default")
      (node (ref "U1") (pin "43") (pinfunction "NC_43") (pintype "passive"))
    )
    (net (code "141") (name "unconnected-(U1-NC-Pad44)") (class "Default")
      (node (ref "U1") (pin "44") (pinfunction "NC_44") (pintype "passive"))
    )
    (net (code "142") (name "unconnected-(U1-NC-Pad47)") (class "Default")
      (node (ref "U1") (pin "47") (pinfunction "NC_47") (pintype "passive"))
    )
    (net (code "143") (name "unconnected-(U1-VCC-Pad18)") (class "Default")
      (node (ref "U1") (pin "18") (pinfunction "VCC_18") (pintype "passive"))
    )
    (net (code "144") (name "unconnected-(U1-VCC-Pad40)") (class "Default")
      (node (ref "U1") (pin "40") (pinfunction "VCC_40") (pintype "passive"))
    )
    (net (code "145") (name "unconnected-(U1-VCC-Pad60)") (class "Default")
      (node (ref "U1") (pin "60") (pinfunction "VCC_60") (pintype "passive"))
    )
    (net (code "146") (name "unconnected-(U1-VCC-Pad68)") (class "Default")
      (node (ref "U1") (pin "68") (pinfunction "VCC_68") (pintype "passive"))
    )
    (net (code "147") (name "unconnected-(U2-DDIS-Pad26)") (class "Default")
      (node (ref "U2") (pin "26") (pinfunction "DDIS_26") (pintype "passive+no_connect"))
    )
    (net (code "148") (name "unconnected-(U2-GND-Pad22)") (class "Default")
      (node (ref "U2") (pin "22") (pinfunction "GND_22") (pintype "passive"))
    )
    (net (code "149") (name "unconnected-(U2-Pad1)") (class "Default")
      (node (ref "U2") (pin "1") (pinfunction "1_1") (pintype "passive"))
    )
    (net (code "150") (name "unconnected-(U2-Pad12)") (class "Default")
      (node (ref "U2") (pin "12") (pinfunction "12_12") (pintype "passive"))
    )
    (net (code "151") (name "unconnected-(U2-Pad23)") (class "Default")
      (node (ref "U2") (pin "23") (pinfunction "23_23") (pintype "passive"))
    )
    (net (code "152") (name "unconnected-(U2-Pad34)") (class "Default")
      (node (ref "U2") (pin "34") (pinfunction "34_34") (pintype "passive"))
    )
    (net (code "153") (name "unconnected-(U2-VCC-Pad44)") (class "Default")
      (node (ref "U2") (pin "44") (pinfunction "VCC_44") (pintype "passive"))
    )
    (net (code "154") (name "unconnected-(U2-XOUT-Pad19)") (class "Default")
      (node (ref "U2") (pin "19") (pinfunction "XOUT_19") (pintype "passive+no_connect"))
    )
    (net (code "155") (name "unconnected-(U2-~{{OUT1}}-Pad38)") (class "Default")
      (node (ref "U2") (pin "38") (pinfunction "~{{OUT1}}_38") (pintype "passive+no_connect"))
    )
    (net (code "156") (name "unconnected-(U2-~{{OUT2}}-Pad35)") (class "Default")
      (node (ref "U2") (pin "35") (pinfunction "~{{OUT2}}_35") (pintype "passive+no_connect"))
    )
    (net (code "157") (name "unconnected-(U2-~{{RXRDY}}-Pad32)") (class "Default")
      (node (ref "U2") (pin "32") (pinfunction "~{{RXRDY}}_32") (pintype "passive+no_connect"))
    )
    (net (code "158") (name "unconnected-(U2-~{{TXRDY}}-Pad27)") (class "Default")
      (node (ref "U2") (pin "27") (pinfunction "~{{TXRDY}}_27") (pintype "passive+no_connect"))
    )
    (net (code "159") (name "unconnected-(U3-GND-Pad11)") (class "Default")
      (node (ref "U3") (pin "11") (pinfunction "GND_11") (pintype "passive"))
    )
    (net (code "160") (name "unconnected-(U3-VCC-Pad20)") (class "Default")
      (node (ref "U3") (pin "20") (pinfunction "VCC_20") (pintype "passive"))
    )
    (net (code "161") (name "unconnected-(U4-GND-Pad14)") (class "Default")
      (node (ref "U4") (pin "14") (pinfunction "GND_14") (pintype "passive"))
    )
    (net (code "162") (name "unconnected-(U4-NC-Pad26)") (class "Default")
      (node (ref "U4") (pin "26") (pinfunction "NC_26") (pintype "passive"))
    )
    (net (code "163") (name "unconnected-(U4-VCC-Pad28)") (class "Default")
      (node (ref "U4") (pin "28") (pinfunction "VCC_28") (pintype "passive"))
    )
    (net (code "164") (name "unconnected-(U5-GND-Pad10)") (class "Default")
      (node (ref "U5") (pin "10") (pinfunction "GND_10") (pintype "passive"))
    )
    (net (code "165") (name "unconnected-(U5-VCC-Pad20)") (class "Default")
      (node (ref "U5") (pin "20") (pinfunction "VCC_20") (pintype "passive"))
    )
    (net (code "166") (name "unconnected-(U6-GND-Pad8)") (class "Default")
      (node (ref "U6") (pin "8") (pinfunction "GND_8") (pintype "passive"))
    )
    (net (code "167") (name "unconnected-(U6-VCC-Pad16)") (class "Default")
      (node (ref "U6") (pin "16") (pinfunction "VCC_16") (pintype "passive"))
    )
    (net (code "168") (name "unconnected-(U6-~{{Y0}}-Pad15)") (class "Default")
      (node (ref "U6") (pin "15") (pinfunction "~{{Y0}}_15") (pintype "passive+no_connect"))
    )
    (net (code "169") (name "unconnected-(U6-~{{Y1}}-Pad14)") (class "Default")
      (node (ref "U6") (pin "14") (pinfunction "~{{Y1}}_14") (pintype "passive+no_connect"))
    )
    (net (code "170") (name "unconnected-(U6-~{{Y2}}-Pad13)") (class "Default")
      (node (ref "U6") (pin "13") (pinfunction "~{{Y2}}_13") (pintype "passive+no_connect"))
    )
    (net (code "171") (name "unconnected-(U6-~{{Y3}}-Pad12)") (class "Default")
      (node (ref "U6") (pin "12") (pinfunction "~{{Y3}}_12") (pintype "passive+no_connect"))
    )
    (net (code "172") (name "unconnected-(U6-~{{Y4}}-Pad11)") (class "Default")
      (node (ref "U6") (pin "11") (pinfunction "~{{Y4}}_11") (pintype "passive+no_connect"))
    )
    (net (code "173") (name "unconnected-(U6-~{{Y5}}-Pad10)") (class "Default")
      (node (ref "U6") (pin "10") (pinfunction "~{{Y5}}_10") (pintype "passive+no_connect"))
    )
    (net (code "174") (name "unconnected-(U6-~{{Y6}}-Pad9)") (class "Default")
      (node (ref "U6") (pin "9") (pinfunction "~{{Y6}}_9") (pintype "passive+no_connect"))
    )
    (net (code "175") (name "unconnected-(U7-GND-Pad8)") (class "Default")
      (node (ref "U7") (pin "8") (pinfunction "GND_8") (pintype "passive"))
    )
    (net (code "176") (name "unconnected-(U7-VCC-Pad16)") (class "Default")
      (node (ref "U7") (pin "16") (pinfunction "VCC_16") (pintype "passive"))
    )
    (net (code "177") (name "unconnected-(U7-~{{Y0}}-Pad15)") (class "Default")
      (node (ref "U7") (pin "15") (pinfunction "~{{Y0}}_15") (pintype "passive+no_connect"))
    )
    (net (code "178") (name "unconnected-(U7-~{{Y1}}-Pad14)") (class "Default")
      (node (ref "U7") (pin "14") (pinfunction "~{{Y1}}_14") (pintype "passive+no_connect"))
    )
    (net (code "179") (name "unconnected-(U7-~{{Y2}}-Pad13)") (class "Default")
      (node (ref "U7") (pin "13") (pinfunction "~{{Y2}}_13") (pintype "passive+no_connect"))
    )
  )
)
